# ST_LINK_V3E.net
KiCad netlist of a schematic drawn in Altium Designer
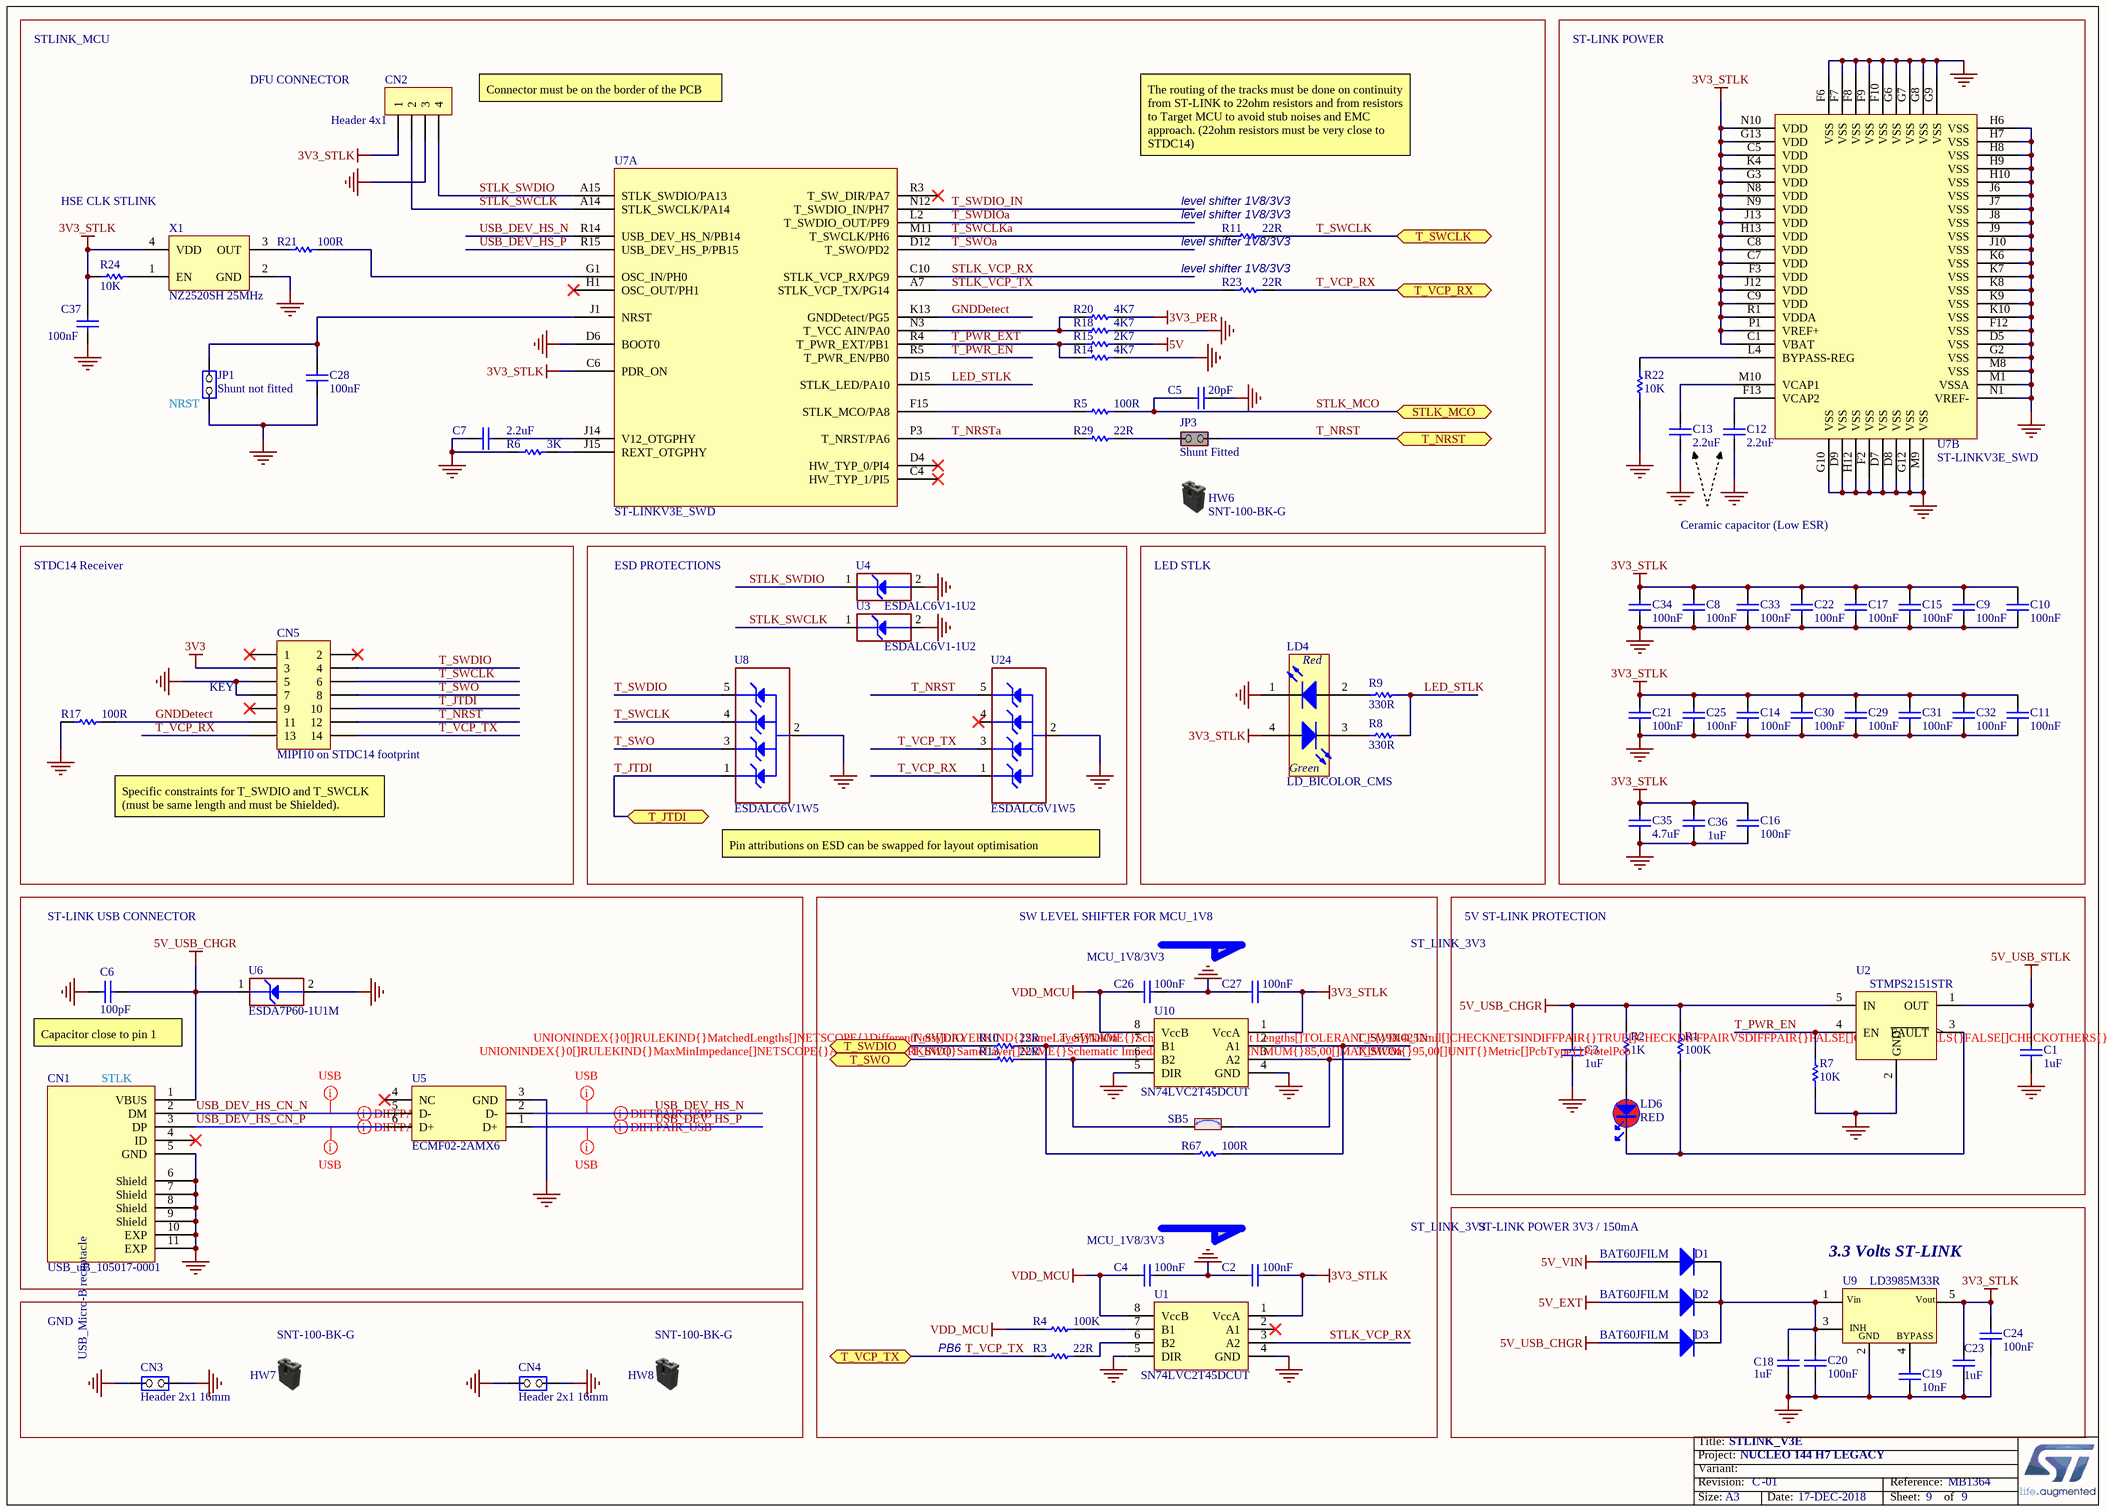
[diagram p0: ST_LINK_V3E.SchDoc]

(export (version "E")
  (design (tool "Eeschema 10.0.6"))
  (components
    (comp (ref "C1")
      (value "1uF")
      (footprint "C0603")
      (description "Capacitor, MLCC, 1uF, 6V3, X5R, 10%, 0603, T=0,8mm")
      (fields
        (field (name "INTERNAL_PART_NUMBER") "MCD-00238")
        (field (name "MANUFACTURER_PART_NUMBER") "CC0603KRX5R5BB105")
        (field (name "PROVIDED_BY") "SUBCO")
      )
      (libsource (lib "MCD_PARTS_database") (part "Capacitor"))
    )
    (comp (ref "C2")
      (value "100nF")
      (footprint "C0603")
      (description "Capacitor, MLCC, 100nF, 6V3, X5R, 10%, 0603, T=0,8mm")
      (fields
        (field (name "INTERNAL_PART_NUMBER") "MCD-00237")
        (field (name "MANUFACTURER_PART_NUMBER") "CC0603KRX5R5BB104")
        (field (name "PROVIDED_BY") "SUBCO")
      )
      (libsource (lib "MCD_PARTS_database") (part "Capacitor"))
    )
    (comp (ref "C3")
      (value "1uF")
      (footprint "C0603")
      (description "Capacitor, MLCC, 1uF, 6V3, X5R, 10%, 0603, T=0,8mm")
      (fields
        (field (name "INTERNAL_PART_NUMBER") "MCD-00238")
        (field (name "MANUFACTURER_PART_NUMBER") "CC0603KRX5R5BB105")
        (field (name "PROVIDED_BY") "SUBCO")
      )
      (libsource (lib "MCD_PARTS_database") (part "Capacitor"))
    )
    (comp (ref "C4")
      (value "100nF")
      (footprint "C0603")
      (description "Capacitor, MLCC, 100nF, 6V3, X5R, 10%, 0603, T=0,8mm")
      (fields
        (field (name "INTERNAL_PART_NUMBER") "MCD-00237")
        (field (name "MANUFACTURER_PART_NUMBER") "CC0603KRX5R5BB104")
        (field (name "PROVIDED_BY") "SUBCO")
      )
      (libsource (lib "MCD_PARTS_database") (part "Capacitor"))
    )
    (comp (ref "C5")
      (value "20pF")
      (footprint "C0402")
      (description "Capacitor, MLCC, 20pF, 50V, NPO, 5%, 0402, T=0,5mm")
      (fields
        (field (name "INTERNAL_PART_NUMBER") "MCD-00016")
        (field (name "MANUFACTURER_PART_NUMBER") "CC0402JRNPO9BN200")
        (field (name "PROVIDED_BY") "SUBCO")
      )
      (libsource (lib "MCD_PARTS_database") (part "Capacitor"))
    )
    (comp (ref "C6")
      (value "100pF")
      (footprint "C0402")
      (description "Capacitor, MLCC, 100pF, 50V, NPO, 5%, 0402, T=0,5mm")
      (fields
        (field (name "INTERNAL_PART_NUMBER") "MCD-00205")
        (field (name "MANUFACTURER_PART_NUMBER") "CC0402JRNPO9BN101")
        (field (name "PROVIDED_BY") "SUBCO")
      )
      (libsource (lib "MCD_PARTS_database") (part "Capacitor"))
    )
    (comp (ref "C7")
      (value "2.2uF")
      (footprint "C0603")
      (description "Capacitor, MLCC, 2.2uF, 10V, X5R, 10%, 0603, T=0,8mm")
      (fields
        (field (name "INTERNAL_PART_NUMBER") "MCD-00012")
        (field (name "MANUFACTURER_PART_NUMBER") "CC0603KRX5R6BB225")
        (field (name "PROVIDED_BY") "SUBCO")
      )
      (libsource (lib "MCD_PARTS_database") (part "Capacitor"))
    )
    (comp (ref "C8")
      (value "100nF")
      (footprint "C0402")
      (description "Capacitor, MLCC, 100nF, 16V, X7R, 10%, 0402, T=0,5mm")
      (fields
        (field (name "INTERNAL_PART_NUMBER") "MCD-00102")
        (field (name "MANUFACTURER_PART_NUMBER") "CC0402KRX7R7BB104")
        (field (name "PROVIDED_BY") "SUBCO")
      )
      (libsource (lib "MCD_PARTS_database") (part "Capacitor"))
    )
    (comp (ref "C9")
      (value "100nF")
      (footprint "C0402")
      (description "Capacitor, MLCC, 100nF, 16V, X7R, 10%, 0402, T=0,5mm")
      (fields
        (field (name "INTERNAL_PART_NUMBER") "MCD-00102")
        (field (name "MANUFACTURER_PART_NUMBER") "CC0402KRX7R7BB104")
        (field (name "PROVIDED_BY") "SUBCO")
      )
      (libsource (lib "MCD_PARTS_database") (part "Capacitor"))
    )
    (comp (ref "C10")
      (value "100nF")
      (footprint "C0402")
      (description "Capacitor, MLCC, 100nF, 16V, X7R, 10%, 0402, T=0,5mm")
      (fields
        (field (name "INTERNAL_PART_NUMBER") "MCD-00102")
        (field (name "MANUFACTURER_PART_NUMBER") "CC0402KRX7R7BB104")
        (field (name "PROVIDED_BY") "SUBCO")
      )
      (libsource (lib "MCD_PARTS_database") (part "Capacitor"))
    )
    (comp (ref "C11")
      (value "100nF")
      (footprint "C0402")
      (description "Capacitor, MLCC, 100nF, 16V, X7R, 10%, 0402, T=0,5mm")
      (fields
        (field (name "INTERNAL_PART_NUMBER") "MCD-00102")
        (field (name "MANUFACTURER_PART_NUMBER") "CC0402KRX7R7BB104")
        (field (name "PROVIDED_BY") "SUBCO")
      )
      (libsource (lib "MCD_PARTS_database") (part "Capacitor"))
    )
    (comp (ref "C12")
      (value "2.2uF")
      (footprint "C0603")
      (description "Capacitor, MLCC, 2.2uF, 10V, X5R, 10%, 0603, T=0,8mm")
      (fields
        (field (name "INTERNAL_PART_NUMBER") "MCD-00012")
        (field (name "MANUFACTURER_PART_NUMBER") "CC0603KRX5R6BB225")
        (field (name "PROVIDED_BY") "SUBCO")
      )
      (libsource (lib "MCD_PARTS_database") (part "Capacitor"))
    )
    (comp (ref "C13")
      (value "2.2uF")
      (footprint "C0603")
      (description "Capacitor, MLCC, 2.2uF, 10V, X5R, 10%, 0603, T=0,8mm")
      (fields
        (field (name "INTERNAL_PART_NUMBER") "MCD-00012")
        (field (name "MANUFACTURER_PART_NUMBER") "CC0603KRX5R6BB225")
        (field (name "PROVIDED_BY") "SUBCO")
      )
      (libsource (lib "MCD_PARTS_database") (part "Capacitor"))
    )
    (comp (ref "C14")
      (value "100nF")
      (footprint "C0402")
      (description "Capacitor, MLCC, 100nF, 16V, X7R, 10%, 0402, T=0,5mm")
      (fields
        (field (name "INTERNAL_PART_NUMBER") "MCD-00102")
        (field (name "MANUFACTURER_PART_NUMBER") "CC0402KRX7R7BB104")
        (field (name "PROVIDED_BY") "SUBCO")
      )
      (libsource (lib "MCD_PARTS_database") (part "Capacitor"))
    )
    (comp (ref "C15")
      (value "100nF")
      (footprint "C0402")
      (description "Capacitor, MLCC, 100nF, 16V, X7R, 10%, 0402, T=0,5mm")
      (fields
        (field (name "INTERNAL_PART_NUMBER") "MCD-00102")
        (field (name "MANUFACTURER_PART_NUMBER") "CC0402KRX7R7BB104")
        (field (name "PROVIDED_BY") "SUBCO")
      )
      (libsource (lib "MCD_PARTS_database") (part "Capacitor"))
    )
    (comp (ref "C16")
      (value "100nF")
      (footprint "C0402")
      (description "Capacitor, MLCC, 100nF, 16V, X7R, 10%, 0402, T=0,5mm")
      (fields
        (field (name "INTERNAL_PART_NUMBER") "MCD-00102")
        (field (name "MANUFACTURER_PART_NUMBER") "CC0402KRX7R7BB104")
        (field (name "PROVIDED_BY") "SUBCO")
      )
      (libsource (lib "MCD_PARTS_database") (part "Capacitor"))
    )
    (comp (ref "C17")
      (value "100nF")
      (footprint "C0402")
      (description "Capacitor, MLCC, 100nF, 16V, X7R, 10%, 0402, T=0,5mm")
      (fields
        (field (name "INTERNAL_PART_NUMBER") "MCD-00102")
        (field (name "MANUFACTURER_PART_NUMBER") "CC0402KRX7R7BB104")
        (field (name "PROVIDED_BY") "SUBCO")
      )
      (libsource (lib "MCD_PARTS_database") (part "Capacitor"))
    )
    (comp (ref "C18")
      (value "1uF")
      (footprint "C0603")
      (description "Capacitor, MLCC, 1uF, 6V3, X5R, 10%, 0603, T=0,8mm")
      (fields
        (field (name "INTERNAL_PART_NUMBER") "MCD-00238")
        (field (name "MANUFACTURER_PART_NUMBER") "CC0603KRX5R5BB105")
        (field (name "PROVIDED_BY") "SUBCO")
      )
      (libsource (lib "MCD_PARTS_database") (part "Capacitor"))
    )
    (comp (ref "C19")
      (value "10nF")
      (footprint "C0402")
      (description "Capacitor, MLCC, 10nF, 16V, X7R, 10%, 0402, T=0.5mm")
      (fields
        (field (name "INTERNAL_PART_NUMBER") "MCD-00011")
        (field (name "MANUFACTURER_PART_NUMBER") "CC0402KRX7R7BB103")
        (field (name "PROVIDED_BY") "SUBCO")
      )
      (libsource (lib "MCD_PARTS_database") (part "Capacitor"))
    )
    (comp (ref "C20")
      (value "100nF")
      (footprint "C0402")
      (description "Capacitor, MLCC, 100nF, 16V, X7R, 10%, 0402, T=0,5mm")
      (fields
        (field (name "INTERNAL_PART_NUMBER") "MCD-00102")
        (field (name "MANUFACTURER_PART_NUMBER") "CC0402KRX7R7BB104")
        (field (name "PROVIDED_BY") "SUBCO")
      )
      (libsource (lib "MCD_PARTS_database") (part "Capacitor"))
    )
    (comp (ref "C21")
      (value "100nF")
      (footprint "C0402")
      (description "Capacitor, MLCC, 100nF, 16V, X7R, 10%, 0402, T=0,5mm")
      (fields
        (field (name "INTERNAL_PART_NUMBER") "MCD-00102")
        (field (name "MANUFACTURER_PART_NUMBER") "CC0402KRX7R7BB104")
        (field (name "PROVIDED_BY") "SUBCO")
      )
      (libsource (lib "MCD_PARTS_database") (part "Capacitor"))
    )
    (comp (ref "C22")
      (value "100nF")
      (footprint "C0402")
      (description "Capacitor, MLCC, 100nF, 16V, X7R, 10%, 0402, T=0,5mm")
      (fields
        (field (name "INTERNAL_PART_NUMBER") "MCD-00102")
        (field (name "MANUFACTURER_PART_NUMBER") "CC0402KRX7R7BB104")
        (field (name "PROVIDED_BY") "SUBCO")
      )
      (libsource (lib "MCD_PARTS_database") (part "Capacitor"))
    )
    (comp (ref "C23")
      (value "1uF")
      (footprint "C0603")
      (description "Capacitor, MLCC, 1uF, 16V, X5R, 10%, 0603, T=0,8mm")
      (fields
        (field (name "INTERNAL_PART_NUMBER") "MCD-00010")
        (field (name "MANUFACTURER_PART_NUMBER") "CC0603KRX5R7BB105")
        (field (name "PROVIDED_BY") "SUBCO")
      )
      (libsource (lib "MCD_PARTS_database") (part "Capacitor"))
    )
    (comp (ref "C24")
      (value "100nF")
      (footprint "C0402")
      (description "Capacitor, MLCC, 100nF, 16V, X7R, 10%, 0402, T=0,5mm")
      (fields
        (field (name "INTERNAL_PART_NUMBER") "MCD-00102")
        (field (name "MANUFACTURER_PART_NUMBER") "CC0402KRX7R7BB104")
        (field (name "PROVIDED_BY") "SUBCO")
      )
      (libsource (lib "MCD_PARTS_database") (part "Capacitor"))
    )
    (comp (ref "C25")
      (value "100nF")
      (footprint "C0402")
      (description "Capacitor, MLCC, 100nF, 16V, X7R, 10%, 0402, T=0,5mm")
      (fields
        (field (name "INTERNAL_PART_NUMBER") "MCD-00102")
        (field (name "MANUFACTURER_PART_NUMBER") "CC0402KRX7R7BB104")
        (field (name "PROVIDED_BY") "SUBCO")
      )
      (libsource (lib "MCD_PARTS_database") (part "Capacitor"))
    )
    (comp (ref "C26")
      (value "100nF")
      (footprint "C0603")
      (description "Capacitor, MLCC, 100nF, 6V3, X5R, 10%, 0603, T=0,8mm")
      (fields
        (field (name "INTERNAL_PART_NUMBER") "MCD-00237")
        (field (name "MANUFACTURER_PART_NUMBER") "CC0603KRX5R5BB104")
        (field (name "PROVIDED_BY") "SUBCO")
      )
      (libsource (lib "MCD_PARTS_database") (part "Capacitor"))
    )
    (comp (ref "C27")
      (value "100nF")
      (footprint "C0603")
      (description "Capacitor, MLCC, 100nF, 6V3, X5R, 10%, 0603, T=0,8mm")
      (fields
        (field (name "INTERNAL_PART_NUMBER") "MCD-00237")
        (field (name "MANUFACTURER_PART_NUMBER") "CC0603KRX5R5BB104")
        (field (name "PROVIDED_BY") "SUBCO")
      )
      (libsource (lib "MCD_PARTS_database") (part "Capacitor"))
    )
    (comp (ref "C28")
      (value "100nF")
      (footprint "C0402")
      (description "Capacitor, MLCC, 100nF, 16V, X7R, 10%, 0402, T=0,5mm")
      (fields
        (field (name "INTERNAL_PART_NUMBER") "MCD-00102")
        (field (name "MANUFACTURER_PART_NUMBER") "CC0402KRX7R7BB104")
        (field (name "PROVIDED_BY") "SUBCO")
      )
      (libsource (lib "MCD_PARTS_database") (part "Capacitor"))
    )
    (comp (ref "C29")
      (value "100nF")
      (footprint "C0402")
      (description "Capacitor, MLCC, 100nF, 16V, X7R, 10%, 0402, T=0,5mm")
      (fields
        (field (name "INTERNAL_PART_NUMBER") "MCD-00102")
        (field (name "MANUFACTURER_PART_NUMBER") "CC0402KRX7R7BB104")
        (field (name "PROVIDED_BY") "SUBCO")
      )
      (libsource (lib "MCD_PARTS_database") (part "Capacitor"))
    )
    (comp (ref "C30")
      (value "100nF")
      (footprint "C0402")
      (description "Capacitor, MLCC, 100nF, 16V, X7R, 10%, 0402, T=0,5mm")
      (fields
        (field (name "INTERNAL_PART_NUMBER") "MCD-00102")
        (field (name "MANUFACTURER_PART_NUMBER") "CC0402KRX7R7BB104")
        (field (name "PROVIDED_BY") "SUBCO")
      )
      (libsource (lib "MCD_PARTS_database") (part "Capacitor"))
    )
    (comp (ref "C31")
      (value "100nF")
      (footprint "C0402")
      (description "Capacitor, MLCC, 100nF, 16V, X7R, 10%, 0402, T=0,5mm")
      (fields
        (field (name "INTERNAL_PART_NUMBER") "MCD-00102")
        (field (name "MANUFACTURER_PART_NUMBER") "CC0402KRX7R7BB104")
        (field (name "PROVIDED_BY") "SUBCO")
      )
      (libsource (lib "MCD_PARTS_database") (part "Capacitor"))
    )
    (comp (ref "C32")
      (value "100nF")
      (footprint "C0402")
      (description "Capacitor, MLCC, 100nF, 16V, X7R, 10%, 0402, T=0,5mm")
      (fields
        (field (name "INTERNAL_PART_NUMBER") "MCD-00102")
        (field (name "MANUFACTURER_PART_NUMBER") "CC0402KRX7R7BB104")
        (field (name "PROVIDED_BY") "SUBCO")
      )
      (libsource (lib "MCD_PARTS_database") (part "Capacitor"))
    )
    (comp (ref "C33")
      (value "100nF")
      (footprint "C0402")
      (description "Capacitor, MLCC, 100nF, 16V, X7R, 10%, 0402, T=0,5mm")
      (fields
        (field (name "INTERNAL_PART_NUMBER") "MCD-00102")
        (field (name "MANUFACTURER_PART_NUMBER") "CC0402KRX7R7BB104")
        (field (name "PROVIDED_BY") "SUBCO")
      )
      (libsource (lib "MCD_PARTS_database") (part "Capacitor"))
    )
    (comp (ref "C34")
      (value "100nF")
      (footprint "C0402")
      (description "Capacitor, MLCC, 100nF, 16V, X7R, 10%, 0402, T=0,5mm")
      (fields
        (field (name "INTERNAL_PART_NUMBER") "MCD-00102")
        (field (name "MANUFACTURER_PART_NUMBER") "CC0402KRX7R7BB104")
        (field (name "PROVIDED_BY") "SUBCO")
      )
      (libsource (lib "MCD_PARTS_database") (part "Capacitor"))
    )
    (comp (ref "C35")
      (value "4.7uF")
      (footprint "C0603")
      (description "Capacitor, MLCC, 4.7uF, 16V, X5R, 10%, 0603, T=0.8mm")
      (fields
        (field (name "INTERNAL_PART_NUMBER") "MCD-00009")
        (field (name "MANUFACTURER_PART_NUMBER") "CC0603KRX5R7BB475")
        (field (name "PROVIDED_BY") "SUBCO")
      )
      (libsource (lib "MCD_PARTS_database") (part "Capacitor"))
    )
    (comp (ref "C36")
      (value "1uF")
      (footprint "C0603")
      (description "Capacitor, MLCC, 1uF, 16V, X5R, 10%, 0603, T=0,8mm")
      (fields
        (field (name "INTERNAL_PART_NUMBER") "MCD-00010")
        (field (name "MANUFACTURER_PART_NUMBER") "CC0603KRX5R7BB105")
        (field (name "PROVIDED_BY") "SUBCO")
      )
      (libsource (lib "MCD_PARTS_database") (part "Capacitor"))
    )
    (comp (ref "C37")
      (value "100nF")
      (footprint "C0402")
      (description "Capacitor, MLCC, 100nF, 16V, X7R, 10%, 0402, T=0,5mm")
      (fields
        (field (name "INTERNAL_PART_NUMBER") "MCD-00102")
        (field (name "MANUFACTURER_PART_NUMBER") "CC0402KRX7R7BB104")
        (field (name "PROVIDED_BY") "SUBCO")
      )
      (libsource (lib "MCD_PARTS_database") (part "Capacitor"))
    )
    (comp (ref "CN1")
      (value "USB_uB_105017-0001")
      (footprint "CON_USBMICROB_MOLEX_105017-0001_H2P90")
      (description "USB-MICRO-B, 0.65mm, RA, SMT, Bottom Mount,")
      (fields
        (field (name "INTERNAL_PART_NUMBER") "MCD-00028")
        (field (name "MANUFACTURER_PART_NUMBER") "1050170001")
        (field (name "PROVIDED_BY") "SUBCO")
      )
      (libsource (lib "MCD_PARTS_database") (part "USB_uB_105017.0001"))
    )
    (comp (ref "CN2")
      (value "Header 4x1")
      (footprint "CON_SAMTEC_TSW-104-07-G-S")
      (description "Header, 4x1, 2,54mm, VR, TH, Height 5.84mm/2.54mm")
      (fields
        (field (name "INTERNAL_PART_NUMBER") "MCD-00029")
        (field (name "MANUFACTURER_PART_NUMBER") "TSW-104-07-x-S")
        (field (name "PROVIDED_BY") "SUBCO")
      )
      (libsource (lib "MCD_PARTS_database") (part "Header 4x1"))
    )
    (comp (ref "CN3")
      (value "Header 2x1 16mm")
      (footprint "CON_SAMTEC_TSW-102-09-X-S")
      (description "Header, 2x1, 2,54mm, VR, TH, Height 5.84mm/10.16mm")
      (fields
        (field (name "INTERNAL_PART_NUMBER") "MCD-00214")
        (field (name "MANUFACTURER_PART_NUMBER") "TSW-102-09-x-S")
        (field (name "PROVIDED_BY") "SUBCO")
      )
      (libsource (lib "MCD_PARTS_database") (part "Jumper_Header 2x1"))
    )
    (comp (ref "CN4")
      (value "Header 2x1 16mm")
      (footprint "CON_SAMTEC_TSW-102-09-X-S")
      (description "Header, 2x1, 2,54mm, VR, TH, Height 5.84mm/10.16mm")
      (fields
        (field (name "INTERNAL_PART_NUMBER") "MCD-00214")
        (field (name "MANUFACTURER_PART_NUMBER") "TSW-102-09-x-S")
        (field (name "PROVIDED_BY") "SUBCO")
      )
      (libsource (lib "MCD_PARTS_database") (part "Jumper_Header 2x1"))
    )
    (comp (ref "CN5")
      (value "MIPI10 on STDC14 footprint")
      (footprint "CON_STDC14_Receiver_MEDIUM_WITH_MIPI10_3D")
      (fields
        (field (name "INTERNAL_PART_NUMBER") "MCD-01226")
        (field (name "MANUFACTURER_PART_NUMBER") "FTSH-105-01-L-DV-K")
        (field (name "MANUFACTURER") "SAMTEC")
        (field (name "PROVIDED_BY") "SUBCO")
      )
      (libsource (lib "MCD_PARTS_database") (part "Header 7x2"))
    )
    (comp (ref "D1")
      (value "BAT60JFILM")
      (footprint "DIO_SOD323")
      (fields
        (field (name "INTERNAL_PART_NUMBER") "MCD-00034")
        (field (name "MANUFACTURER") "STMICROELECTRONICS")
        (field (name "BMS_PART_NUMBER") "9151097")
        (field (name "PROVIDED_BY") "SUBCO with ST control")
      )
      (libsource (lib "MCD_PARTS_database") (part "BAT60JFILM"))
    )
    (comp (ref "D2")
      (value "BAT60JFILM")
      (footprint "DIO_SOD323")
      (fields
        (field (name "INTERNAL_PART_NUMBER") "MCD-00034")
        (field (name "MANUFACTURER") "STMICROELECTRONICS")
        (field (name "BMS_PART_NUMBER") "9151097")
        (field (name "PROVIDED_BY") "SUBCO with ST control")
      )
      (libsource (lib "MCD_PARTS_database") (part "BAT60JFILM"))
    )
    (comp (ref "D3")
      (value "BAT60JFILM")
      (footprint "DIO_SOD323")
      (fields
        (field (name "INTERNAL_PART_NUMBER") "MCD-00034")
        (field (name "MANUFACTURER") "STMICROELECTRONICS")
        (field (name "BMS_PART_NUMBER") "9151097")
        (field (name "PROVIDED_BY") "SUBCO with ST control")
      )
      (libsource (lib "MCD_PARTS_database") (part "BAT60JFILM"))
    )
    (comp (ref "HW6")
      (value "SNT-100-BK-G")
      (description "SHUNT 2.54mm BLACK")
      (fields
        (field (name "INTERNAL_PART_NUMBER") "MCD-00043")
        (field (name "MANUFACTURER") "SAMTEC")
        (field (name "PROVIDED_BY") "SUBCO")
      )
      (libsource (lib "MCD_PARTS_database") (part "Shunt Black 2.54mm"))
    )
    (comp (ref "HW7")
      (value "SNT-100-BK-G")
      (description "SHUNT 2.54mm BLACK")
      (fields
        (field (name "INTERNAL_PART_NUMBER") "MCD-00043")
        (field (name "MANUFACTURER") "SAMTEC")
        (field (name "PROVIDED_BY") "SUBCO")
      )
      (libsource (lib "MCD_PARTS_database") (part "Shunt Black 2.54mm"))
    )
    (comp (ref "HW8")
      (value "SNT-100-BK-G")
      (description "SHUNT 2.54mm BLACK")
      (fields
        (field (name "INTERNAL_PART_NUMBER") "MCD-00043")
        (field (name "MANUFACTURER") "SAMTEC")
        (field (name "PROVIDED_BY") "SUBCO")
      )
      (libsource (lib "MCD_PARTS_database") (part "Shunt Black 2.54mm"))
    )
    (comp (ref "JP1")
      (value "Shunt not fitted")
      (footprint "CON_SAMTEC_TSW-102-07-G-S")
      (description "Header, 2x1, 2,54mm, VR, TH, Height 5.84mm/2.54mm")
      (fields
        (field (name "INTERNAL_PART_NUMBER") "MCD-00045")
        (field (name "MANUFACTURER_PART_NUMBER") "TSW-102-07-x-S")
        (field (name "PROVIDED_BY") "SUBCO")
      )
      (libsource (lib "MCD_PARTS_database") (part "Jumper_Header 2x1"))
    )
    (comp (ref "JP3")
      (value "Shunt Fitted")
      (footprint "CON_SAMTEC_TSW-102-07-G-S")
      (description "Header, 2x1, 2,54mm, VR, TH, Height 5.84mm/2.54mm - Shunt Fitted by default")
      (fields
        (field (name "INTERNAL_PART_NUMBER") "MCD-00683")
        (field (name "MANUFACTURER_PART_NUMBER") "TSW-102-07-x-S")
        (field (name "PROVIDED_BY") "SUBCO")
      )
      (libsource (lib "MCD_PARTS_database") (part "Jumper_Header 2x1 Fitted"))
    )
    (comp (ref "LD4")
      (value "LD_BICOLOR_CMS")
      (footprint "LED_BI-GR_HSMF-A201-A00J1")
      (description "LED Bicolor")
      (fields
        (field (name "INTERNAL_PART_NUMBER") "MCD-00051")
        (field (name "MANUFACTURER_PART_NUMBER") "HSMF-A201-A00J1")
        (field (name "PROVIDED_BY") "SUBCO")
      )
      (libsource (lib "MCD_PARTS_database") (part "LD_BICOLOR_CMS"))
    )
    (comp (ref "LD6")
      (value "RED")
      (footprint "LED_0603_RED")
      (description "LED, Red, 0603")
      (fields
        (field (name "INTERNAL_PART_NUMBER") "MCD-00049")
        (field (name "MANUFACTURER_PART_NUMBER") "19-213-R6C-AP1Q2B/3T")
        (field (name "PROVIDED_BY") "SUBCO")
      )
      (libsource (lib "MCD_PARTS_database") (part "LED_red"))
    )
    (comp (ref "R1")
      (value "100K")
      (footprint "R0603")
      (description "Resistor,100K,0603,1%,1/10W")
      (fields
        (field (name "INTERNAL_PART_NUMBER") "MCD-00223")
        (field (name "MANUFACTURER_PART_NUMBER") "RC0603FR-07100KL")
        (field (name "PROVIDED_BY") "SUBCO")
      )
      (libsource (lib "MCD_PARTS_database") (part "Resistor"))
    )
    (comp (ref "R2")
      (value "1K")
      (footprint "R0603")
      (description "Resistor,1K,0603,1%,1/10W")
      (fields
        (field (name "INTERNAL_PART_NUMBER") "MCD-00070")
        (field (name "MANUFACTURER_PART_NUMBER") "RC0603FR-071KL")
        (field (name "PROVIDED_BY") "SUBCO")
      )
      (libsource (lib "MCD_PARTS_database") (part "Resistor"))
    )
    (comp (ref "R3")
      (value "22R")
      (footprint "R0402")
      (description "Resistor,22R,0402,1%,1/16W")
      (fields
        (field (name "INTERNAL_PART_NUMBER") "MCD-00189")
        (field (name "MANUFACTURER_PART_NUMBER") "RC0402FR-0722RL")
        (field (name "PROVIDED_BY") "SUBCO")
      )
      (libsource (lib "MCD_PARTS_database") (part "Resistor"))
    )
    (comp (ref "R4")
      (value "100K")
      (footprint "R0603")
      (description "Resistor,100K,0603,1%,1/10W")
      (fields
        (field (name "INTERNAL_PART_NUMBER") "MCD-00223")
        (field (name "MANUFACTURER_PART_NUMBER") "RC0603FR-07100KL")
        (field (name "PROVIDED_BY") "SUBCO")
      )
      (libsource (lib "MCD_PARTS_database") (part "Resistor"))
    )
    (comp (ref "R5")
      (value "100R")
      (footprint "R0402")
      (description "Resistor,100R,0402,1%,1/16W")
      (fields
        (field (name "INTERNAL_PART_NUMBER") "MCD-00119")
        (field (name "MANUFACTURER_PART_NUMBER") "RC0402FR-07100RL")
        (field (name "PROVIDED_BY") "SUBCO")
      )
      (libsource (lib "MCD_PARTS_database") (part "Resistor"))
    )
    (comp (ref "R6")
      (value "3K")
      (footprint "R0402")
      (description "Resistor,3K,0402,1%,1/16W")
      (fields
        (field (name "INTERNAL_PART_NUMBER") "MCD-00185")
        (field (name "MANUFACTURER_PART_NUMBER") "RC0402FR-073KL")
        (field (name "PROVIDED_BY") "SUBCO")
      )
      (libsource (lib "MCD_PARTS_database") (part "Resistor"))
    )
    (comp (ref "R7")
      (value "10K")
      (footprint "R0603")
      (description "Resistor,10K,0603,1%,1/10W")
      (fields
        (field (name "INTERNAL_PART_NUMBER") "MCD-00220")
        (field (name "MANUFACTURER_PART_NUMBER") "RC0603FR-0710KL")
        (field (name "PROVIDED_BY") "SUBCO")
      )
      (libsource (lib "MCD_PARTS_database") (part "Resistor"))
    )
    (comp (ref "R8")
      (value "330R")
      (footprint "R0603")
      (description "Resistor,330R,0603,1%,1/10W")
      (fields
        (field (name "INTERNAL_PART_NUMBER") "MCD-00197")
        (field (name "MANUFACTURER_PART_NUMBER") "RC0603FR-07330RL")
        (field (name "PROVIDED_BY") "SUBCO")
      )
      (libsource (lib "MCD_PARTS_database") (part "Resistor"))
    )
    (comp (ref "R9")
      (value "330R")
      (footprint "R0603")
      (description "Resistor,330R,0603,1%,1/10W")
      (fields
        (field (name "INTERNAL_PART_NUMBER") "MCD-00197")
        (field (name "MANUFACTURER_PART_NUMBER") "RC0603FR-07330RL")
        (field (name "PROVIDED_BY") "SUBCO")
      )
      (libsource (lib "MCD_PARTS_database") (part "Resistor"))
    )
    (comp (ref "R10")
      (value "22R")
      (footprint "R0402")
      (description "Resistor,22R,0402,1%,1/16W")
      (fields
        (field (name "INTERNAL_PART_NUMBER") "MCD-00189")
        (field (name "MANUFACTURER_PART_NUMBER") "RC0402FR-0722RL")
        (field (name "PROVIDED_BY") "SUBCO")
      )
      (libsource (lib "MCD_PARTS_database") (part "Resistor"))
    )
    (comp (ref "R11")
      (value "22R")
      (footprint "R0402")
      (description "Resistor,22R,0402,1%,1/16W")
      (fields
        (field (name "INTERNAL_PART_NUMBER") "MCD-00189")
        (field (name "MANUFACTURER_PART_NUMBER") "RC0402FR-0722RL")
        (field (name "PROVIDED_BY") "SUBCO")
      )
      (libsource (lib "MCD_PARTS_database") (part "Resistor"))
    )
    (comp (ref "R13")
      (value "22R")
      (footprint "R0402")
      (description "Resistor,22R,0402,1%,1/16W")
      (fields
        (field (name "INTERNAL_PART_NUMBER") "MCD-00189")
        (field (name "MANUFACTURER_PART_NUMBER") "RC0402FR-0722RL")
        (field (name "PROVIDED_BY") "SUBCO")
      )
      (libsource (lib "MCD_PARTS_database") (part "Resistor"))
    )
    (comp (ref "R14")
      (value "4K7")
      (footprint "R0402")
      (description "Resistor,4K7,0402,1%,1/16W")
      (fields
        (field (name "INTERNAL_PART_NUMBER") "MCD-00065")
        (field (name "MANUFACTURER_PART_NUMBER") "RC0402FR-074K7L")
        (field (name "PROVIDED_BY") "SUBCO")
      )
      (libsource (lib "MCD_PARTS_database") (part "Resistor"))
    )
    (comp (ref "R15")
      (value "2K7")
      (footprint "R0402")
      (description "Resistor,2K7,0402,1%,1/16W")
      (fields
        (field (name "INTERNAL_PART_NUMBER") "MCD-00055")
        (field (name "MANUFACTURER_PART_NUMBER") "RC0402FR-072K7L")
        (field (name "PROVIDED_BY") "SUBCO")
      )
      (libsource (lib "MCD_PARTS_database") (part "Resistor"))
    )
    (comp (ref "R17")
      (value "100R")
      (footprint "R0402")
      (description "Resistor,100R,0402,1%,1/16W")
      (fields
        (field (name "INTERNAL_PART_NUMBER") "MCD-00119")
        (field (name "MANUFACTURER_PART_NUMBER") "RC0402FR-07100RL")
        (field (name "PROVIDED_BY") "SUBCO")
      )
      (libsource (lib "MCD_PARTS_database") (part "Resistor"))
    )
    (comp (ref "R18")
      (value "4K7")
      (footprint "R0402")
      (description "Resistor,4K7,0402,1%,1/16W")
      (fields
        (field (name "INTERNAL_PART_NUMBER") "MCD-00065")
        (field (name "MANUFACTURER_PART_NUMBER") "RC0402FR-074K7L")
        (field (name "PROVIDED_BY") "SUBCO")
      )
      (libsource (lib "MCD_PARTS_database") (part "Resistor"))
    )
    (comp (ref "R20")
      (value "4K7")
      (footprint "R0402")
      (description "Resistor,4K7,0402,1%,1/16W")
      (fields
        (field (name "INTERNAL_PART_NUMBER") "MCD-00065")
        (field (name "MANUFACTURER_PART_NUMBER") "RC0402FR-074K7L")
        (field (name "PROVIDED_BY") "SUBCO")
      )
      (libsource (lib "MCD_PARTS_database") (part "Resistor"))
    )
    (comp (ref "R21")
      (value "100R")
      (footprint "R0402")
      (description "Resistor,100R,0402,1%,1/16W")
      (fields
        (field (name "INTERNAL_PART_NUMBER") "MCD-00119")
        (field (name "MANUFACTURER_PART_NUMBER") "RC0402FR-07100RL")
        (field (name "PROVIDED_BY") "SUBCO")
      )
      (libsource (lib "MCD_PARTS_database") (part "Resistor"))
    )
    (comp (ref "R22")
      (value "10K")
      (footprint "R0402")
      (description "Resistor,10K,0402,1%,1/16W")
      (fields
        (field (name "INTERNAL_PART_NUMBER") "MCD-00053")
        (field (name "MANUFACTURER_PART_NUMBER") "RC0402FR-0710KL")
        (field (name "PROVIDED_BY") "SUBCO")
      )
      (libsource (lib "MCD_PARTS_database") (part "Resistor"))
    )
    (comp (ref "R23")
      (value "22R")
      (footprint "R0402")
      (description "Resistor,22R,0402,1%,1/16W")
      (fields
        (field (name "INTERNAL_PART_NUMBER") "MCD-00189")
        (field (name "MANUFACTURER_PART_NUMBER") "RC0402FR-0722RL")
        (field (name "PROVIDED_BY") "SUBCO")
      )
      (libsource (lib "MCD_PARTS_database") (part "Resistor"))
    )
    (comp (ref "R24")
      (value "10K")
      (footprint "R0402")
      (description "Resistor,10K,0402,1%,1/16W")
      (fields
        (field (name "INTERNAL_PART_NUMBER") "MCD-00053")
        (field (name "MANUFACTURER_PART_NUMBER") "RC0402FR-0710KL")
        (field (name "PROVIDED_BY") "SUBCO")
      )
      (libsource (lib "MCD_PARTS_database") (part "Resistor"))
    )
    (comp (ref "R29")
      (value "22R")
      (footprint "R0402")
      (description "Resistor,22R,0402,1%,1/16W")
      (fields
        (field (name "INTERNAL_PART_NUMBER") "MCD-00189")
        (field (name "MANUFACTURER_PART_NUMBER") "RC0402FR-0722RL")
        (field (name "PROVIDED_BY") "SUBCO")
      )
      (libsource (lib "MCD_PARTS_database") (part "Resistor"))
    )
    (comp (ref "R67")
      (value "100R")
      (footprint "R0402")
      (description "Resistor,100R,0402,1%,1/16W")
      (fields
        (field (name "INTERNAL_PART_NUMBER") "MCD-00119")
        (field (name "MANUFACTURER_PART_NUMBER") "RC0402FR-07100RL")
        (field (name "PROVIDED_BY") "SUBCO")
      )
      (libsource (lib "MCD_PARTS_database") (part "Resistor"))
    )
    (comp (ref "SB5")
      (value "SB_ON")
      (footprint "SOLDER-BRIDGE_R0603-0R")
      (description "Solder Bridge ON")
      (fields
        (field (name "INTERNAL_PART_NUMBER") "MCD-00071")
        (field (name "MANUFACTURER_PART_NUMBER") "RC0603JR-070RL")
        (field (name "PROVIDED_BY") "SUBCO")
      )
      (libsource (lib "MCD_PARTS_database") (part "SB_ON"))
    )
    (comp (ref "U1")
      (value "SN74LVC2T45DCUT")
      (footprint "ICC_VSSOP8_DCU_R-PDSO-G8_2X2P30_P050")
      (description "Dual bit dual supply bus transceiver")
      (fields
        (field (name "INTERNAL_PART_NUMBER") "MCD-00264")
        (field (name "MANUFACTURER") "TEXAS INSTRUMENTS")
        (field (name "PROVIDED_BY") "SUBCO")
      )
      (libsource (lib "MCD_PARTS_database") (part "SN74LVC2T45DCUT"))
    )
    (comp (ref "U2")
      (value "STMPS2151STR")
      (footprint "MOS_SOT23-5L")
      (description "500mA, Enhanced single channel power switches with active high enable pin")
      (fields
        (field (name "INTERNAL_PART_NUMBER") "MCD-00159")
        (field (name "MANUFACTURER") "STMICROELECTRONICS")
        (field (name "PROVIDED_BY") "SUBCO with ST control")
      )
      (libsource (lib "MCD_PARTS_database") (part "STMPS2151STR"))
    )
    (comp (ref "U3")
      (value "ESDALC6V1-1U2")
      (footprint "ESD_ST0201")
      (description "ESD protection 6V1")
      (fields
        (field (name "INTERNAL_PART_NUMBER") "MCD-00170")
        (field (name "MANUFACTURER") "STMICROELECTRONICS")
        (field (name "PROVIDED_BY") "SUBCO with ST control")
      )
      (libsource (lib "MCD_PARTS_database") (part "ESD-TRANSIL"))
    )
    (comp (ref "U4")
      (value "ESDALC6V1-1U2")
      (footprint "ESD_ST0201")
      (description "ESD protection 6V1")
      (fields
        (field (name "INTERNAL_PART_NUMBER") "MCD-00170")
        (field (name "MANUFACTURER") "STMICROELECTRONICS")
        (field (name "PROVIDED_BY") "SUBCO with ST control")
      )
      (libsource (lib "MCD_PARTS_database") (part "ESD-TRANSIL"))
    )
    (comp (ref "U5")
      (value "ECMF02-2AMX6")
      (footprint "ESD_QFN-6L_1P7X1P5_P050")
      (description "Common mode filter with ESD protection for USB 2.0 interface")
      (fields
        (field (name "INTERNAL_PART_NUMBER") "MCD-00649")
        (field (name "MANUFACTURER") "STMICROELECTRONICS")
        (field (name "PROVIDED_BY") "SUBCO with ST control")
      )
      (libsource (lib "MCD_PARTS_database") (part "ECMF02-2AMX6"))
    )
    (comp (ref "U6")
      (value "ESDA7P60-1U1M")
      (footprint "ESD_QFN2_1P6X1_P125")
      (description "High power transient voltage suppressor, 7V breakdown")
      (fields
        (field (name "INTERNAL_PART_NUMBER") "MCD-00251")
        (field (name "MANUFACTURER") "STMICROELECTRONICS")
        (field (name "PROVIDED_BY") "SUBCO with ST control")
      )
      (libsource (lib "MCD_PARTS_database") (part "ESD-TRANSIL"))
    )
    (comp (ref "U7")
      (value "ST-LINKV3E_SWD")
      (footprint "ICC_UFBGA201_176+25_10X10_P065")
      (description "STM32F723IEK  (STM32F7) BGA176")
      (fields
        (field (name "INTERNAL_PART_NUMBER") "MCD-00596")
        (field (name "MANUFACTURER_PART_NUMBER") "STM32F723IEK6")
        (field (name "PROVIDED_BY") "SUBCO with ST control")
      )
      (libsource (lib "MCD_PARTS_database") (part "ST-LINKV3E_SWD"))
    )
    (comp (ref "U8")
      (value "ESDALC6V1W5")
      (footprint "ESD_SOT323-5L")
      (description "Dual Transil array for ESD protection")
      (fields
        (field (name "INTERNAL_PART_NUMBER") "MCD-00136")
        (field (name "MANUFACTURER") "STMICROELECTRONICS")
        (field (name "PROVIDED_BY") "SUBCO with ST control")
      )
      (libsource (lib "MCD_PARTS_database") (part "ESDALC6V1W5"))
    )
    (comp (ref "U9")
      (value "LD3985M33R")
      (footprint "REG_SOT23-5L")
      (description "Ultra low drop-low noise BiCMOS voltage, regulators low ESR capacitors compatible")
      (fields
        (field (name "INTERNAL_PART_NUMBER") "MCD-00086")
        (field (name "MANUFACTURER") "STMICROELECTRONICS")
        (field (name "PROVIDED_BY") "SUBCO with ST control")
      )
      (libsource (lib "MCD_PARTS_database") (part "LD3985M33R"))
    )
    (comp (ref "U10")
      (value "SN74LVC2T45DCUT")
      (footprint "ICC_VSSOP8_DCU_R-PDSO-G8_2X2P30_P050")
      (description "Dual bit dual supply bus transceiver")
      (fields
        (field (name "INTERNAL_PART_NUMBER") "MCD-00264")
        (field (name "MANUFACTURER") "TEXAS INSTRUMENTS")
        (field (name "PROVIDED_BY") "SUBCO")
      )
      (libsource (lib "MCD_PARTS_database") (part "SN74LVC2T45DCUT"))
    )
    (comp (ref "U24")
      (value "ESDALC6V1W5")
      (footprint "ESD_SOT323-5L")
      (description "Dual Transil array for ESD protection")
      (fields
        (field (name "INTERNAL_PART_NUMBER") "MCD-00136")
        (field (name "MANUFACTURER") "STMICROELECTRONICS")
        (field (name "PROVIDED_BY") "SUBCO with ST control")
      )
      (libsource (lib "MCD_PARTS_database") (part "ESDALC6V1W5"))
    )
    (comp (ref "X1")
      (value "NZ2520SH 25MHz")
      (footprint "OSC_NDK_NZ2520SB_4P")
      (description "Oscillator 25Mhz, +-50ppm, Vcc:3.3V typ, square wave: [0.1Vcc;0.9Vcc], Enable pin, SMD")
      (fields
        (field (name "INTERNAL_PART_NUMBER") "MCD-00597")
        (field (name "MANUFACTURER_PART_NUMBER") "NZ2520SH 25MHz END4869C")
        (field (name "PROVIDED_BY") "SUBCO")
      )
      (libsource (lib "MCD_PARTS_database") (part "OSCILLATOR_4_PINS"))
    )
  )
  (nets
    (net (code "2") (name "/GNDDetect") (class "Default")
      (node (ref "CN5") (pin "11") (pinfunction "11_11") (pintype "passive"))
      (node (ref "R17") (pin "2") (pinfunction "2_2") (pintype "passive"))
      (node (ref "U7") (pin "K13") (pinfunction "GNDDetect/PG5_K13") (pintype "passive"))
    )
    (net (code "3") (name "/LED_STLK") (class "Default")
      (node (ref "R8") (pin "2") (pinfunction "2_2") (pintype "passive"))
      (node (ref "R9") (pin "2") (pinfunction "2_2") (pintype "passive"))
      (node (ref "U7") (pin "D15") (pinfunction "STLK_LED/PA10_D15") (pintype "passive"))
    )
    (net (code "4") (name "/STLK_MCO") (class "Default")
      (node (ref "C5") (pin "2") (pinfunction "2_2") (pintype "passive"))
      (node (ref "R5") (pin "2") (pinfunction "2_2") (pintype "passive"))
    )
    (net (code "5") (name "/STLK_SWCLK") (class "Default")
      (node (ref "CN2") (pin "2") (pinfunction "2_2") (pintype "passive"))
      (node (ref "U3") (pin "1") (pinfunction "IO1_1") (pintype "passive"))
      (node (ref "U7") (pin "A14") (pinfunction "STLK_SWCLK/PA14_A14") (pintype "passive"))
    )
    (net (code "6") (name "/STLK_SWDIO") (class "Default")
      (node (ref "CN2") (pin "4") (pinfunction "4_4") (pintype "passive"))
      (node (ref "U4") (pin "1") (pinfunction "IO1_1") (pintype "passive"))
      (node (ref "U7") (pin "A15") (pinfunction "STLK_SWDIO/PA13_A15") (pintype "passive"))
    )
    (net (code "7") (name "/STLK_VCP_RX") (class "Default")
      (node (ref "U1") (pin "3") (pinfunction "A2_3") (pintype "passive"))
      (node (ref "U7") (pin "C10") (pinfunction "STLK_VCP_RX/PG9_C10") (pintype "passive"))
    )
    (net (code "8") (name "/STLK_VCP_TX") (class "Default")
      (node (ref "R23") (pin "1") (pinfunction "1_1") (pintype "passive"))
      (node (ref "U7") (pin "A7") (pinfunction "STLK_VCP_TX/PG14_A7") (pintype "passive"))
    )
    (net (code "9") (name "/T_JTDI") (class "Default")
      (node (ref "CN5") (pin "10") (pinfunction "10_10") (pintype "passive"))
      (node (ref "U8") (pin "1") (pinfunction "IO1_1") (pintype "passive"))
    )
    (net (code "10") (name "/T_NRST") (class "Default")
      (node (ref "CN5") (pin "12") (pinfunction "12_12") (pintype "passive"))
      (node (ref "JP3") (pin "2") (pinfunction "NO_2") (pintype "passive"))
      (node (ref "U24") (pin "5") (pinfunction "IO4_5") (pintype "passive"))
    )
    (net (code "11") (name "/T_NRSTa") (class "Default")
      (node (ref "R29") (pin "1") (pinfunction "1_1") (pintype "passive"))
      (node (ref "U7") (pin "P3") (pinfunction "T_NRST/PA6_P3") (pintype "passive"))
    )
    (net (code "12") (name "/T_PWR_EN") (class "Default")
      (node (ref "R7") (pin "1") (pinfunction "1_1") (pintype "passive"))
      (node (ref "U2") (pin "4") (pinfunction "EN_4") (pintype "passive"))
      (node (ref "U7") (pin "R5") (pinfunction "T_PWR_EN/PB0_R5") (pintype "passive"))
    )
    (net (code "13") (name "/T_PWR_EXT") (class "Default")
      (node (ref "R14") (pin "2") (pinfunction "2_2") (pintype "passive"))
      (node (ref "R15") (pin "2") (pinfunction "2_2") (pintype "passive"))
      (node (ref "U7") (pin "R4") (pinfunction "T_PWR_EXT/PB1_R4") (pintype "passive"))
    )
    (net (code "14") (name "/T_SWCLK") (class "Default")
      (node (ref "CN5") (pin "6") (pinfunction "6_6") (pintype "passive"))
      (node (ref "R11") (pin "2") (pinfunction "2_2") (pintype "passive"))
      (node (ref "U8") (pin "4") (pinfunction "IO3_4") (pintype "passive"))
    )
    (net (code "15") (name "/T_SWCLKa") (class "Default")
      (node (ref "R11") (pin "1") (pinfunction "1_1") (pintype "passive"))
      (node (ref "U7") (pin "M11") (pinfunction "T_SWCLK/PH6_M11") (pintype "passive"))
    )
    (net (code "16") (name "/T_SWDIO") (class "Default")
      (node (ref "CN5") (pin "4") (pinfunction "4_4") (pintype "passive"))
      (node (ref "R10") (pin "1") (pinfunction "1_1") (pintype "passive"))
      (node (ref "U8") (pin "5") (pinfunction "IO4_5") (pintype "passive"))
    )
    (net (code "17") (name "/T_SWDIO_IN") (class "Default")
      (node (ref "R67") (pin "2") (pinfunction "2_2") (pintype "passive"))
      (node (ref "U10") (pin "2") (pinfunction "A1_2") (pintype "passive"))
      (node (ref "U7") (pin "N12") (pinfunction "T_SWDIO_IN/PH7_N12") (pintype "passive"))
    )
    (net (code "18") (name "/T_SWDIOa") (class "Default")
      (node (ref "R10") (pin "2") (pinfunction "2_2") (pintype "passive"))
      (node (ref "R67") (pin "1") (pinfunction "1_1") (pintype "passive"))
      (node (ref "U10") (pin "7") (pinfunction "B1_7") (pintype "passive"))
      (node (ref "U7") (pin "L2") (pinfunction "T_SWDIO_OUT/PF9_L2") (pintype "passive"))
    )
    (net (code "19") (name "/T_SWO") (class "Default")
      (node (ref "CN5") (pin "8") (pinfunction "8_8") (pintype "passive"))
      (node (ref "R13") (pin "1") (pinfunction "1_1") (pintype "passive"))
      (node (ref "U8") (pin "3") (pinfunction "IO2_3") (pintype "passive"))
    )
    (net (code "20") (name "/T_SWOa") (class "Default")
      (node (ref "SB5") (pin "1") (pinfunction "1_1") (pintype "passive"))
      (node (ref "U10") (pin "3") (pinfunction "A2_3") (pintype "passive"))
      (node (ref "U7") (pin "D12") (pinfunction "T_SWO/PD2_D12") (pintype "passive"))
    )
    (net (code "21") (name "/T_VCP_RX") (class "Default")
      (node (ref "CN5") (pin "13") (pinfunction "13_13") (pintype "passive"))
      (node (ref "R23") (pin "2") (pinfunction "2_2") (pintype "passive"))
      (node (ref "U24") (pin "1") (pinfunction "IO1_1") (pintype "passive"))
    )
    (net (code "22") (name "/T_VCP_TX") (class "Default")
      (node (ref "CN5") (pin "14") (pinfunction "14_14") (pintype "passive"))
      (node (ref "R3") (pin "1") (pinfunction "1_1") (pintype "passive"))
      (node (ref "U24") (pin "3") (pinfunction "IO2_3") (pintype "passive"))
    )
    (net (code "23") (name "/USB_DEV_HS_CN_N") (class "Default")
      (node (ref "CN1") (pin "2") (pinfunction "DM_2") (pintype "passive"))
      (node (ref "U5") (pin "5") (pinfunction "D-_5") (pintype "passive"))
    )
    (net (code "24") (name "/USB_DEV_HS_CN_P") (class "Default")
      (node (ref "CN1") (pin "3") (pinfunction "DP_3") (pintype "passive"))
      (node (ref "U5") (pin "6") (pinfunction "D+_6") (pintype "passive"))
    )
    (net (code "25") (name "/USB_DEV_HS_N") (class "Default")
      (node (ref "U5") (pin "2") (pinfunction "D-_2") (pintype "passive"))
      (node (ref "U7") (pin "R14") (pinfunction "USB_DEV_HS_N/PB14_R14") (pintype "passive"))
    )
    (net (code "26") (name "/USB_DEV_HS_P") (class "Default")
      (node (ref "U5") (pin "1") (pinfunction "D+_1") (pintype "passive"))
      (node (ref "U7") (pin "R15") (pinfunction "USB_DEV_HS_P/PB15_R15") (pintype "passive"))
    )
    (net (code "27") (name "3V3") (class "Default")
      (node (ref "CN5") (pin "3") (pinfunction "3_3") (pintype "passive"))
    )
    (net (code "28") (name "3V3_PER") (class "Default")
      (node (ref "R20") (pin "2") (pinfunction "2_2") (pintype "passive"))
    )
    (net (code "29") (name "3V3_STLK") (class "Default")
      (node (ref "C10") (pin "2") (pinfunction "2_2") (pintype "passive"))
      (node (ref "C11") (pin "2") (pinfunction "2_2") (pintype "passive"))
      (node (ref "C14") (pin "2") (pinfunction "2_2") (pintype "passive"))
      (node (ref "C15") (pin "2") (pinfunction "2_2") (pintype "passive"))
      (node (ref "C16") (pin "2") (pinfunction "2_2") (pintype "passive"))
      (node (ref "C17") (pin "2") (pinfunction "2_2") (pintype "passive"))
      (node (ref "C2") (pin "2") (pinfunction "2_2") (pintype "passive"))
      (node (ref "C21") (pin "2") (pinfunction "2_2") (pintype "passive"))
      (node (ref "C22") (pin "2") (pinfunction "2_2") (pintype "passive"))
      (node (ref "C23") (pin "2") (pinfunction "2_2") (pintype "passive"))
      (node (ref "C24") (pin "2") (pinfunction "2_2") (pintype "passive"))
      (node (ref "C25") (pin "2") (pinfunction "2_2") (pintype "passive"))
      (node (ref "C27") (pin "2") (pinfunction "2_2") (pintype "passive"))
      (node (ref "C29") (pin "2") (pinfunction "2_2") (pintype "passive"))
      (node (ref "C30") (pin "2") (pinfunction "2_2") (pintype "passive"))
      (node (ref "C31") (pin "2") (pinfunction "2_2") (pintype "passive"))
      (node (ref "C32") (pin "2") (pinfunction "2_2") (pintype "passive"))
      (node (ref "C33") (pin "2") (pinfunction "2_2") (pintype "passive"))
      (node (ref "C34") (pin "2") (pinfunction "2_2") (pintype "passive"))
      (node (ref "C35") (pin "2") (pinfunction "2_2") (pintype "passive"))
      (node (ref "C36") (pin "2") (pinfunction "2_2") (pintype "passive"))
      (node (ref "C37") (pin "2") (pinfunction "2_2") (pintype "passive"))
      (node (ref "C8") (pin "2") (pinfunction "2_2") (pintype "passive"))
      (node (ref "C9") (pin "2") (pinfunction "2_2") (pintype "passive"))
      (node (ref "CN2") (pin "1") (pinfunction "1_1") (pintype "passive"))
      (node (ref "LD4") (pin "4") (pinfunction "YellowGreen_anode_4") (pintype "passive"))
      (node (ref "R24") (pin "1") (pinfunction "1_1") (pintype "passive"))
      (node (ref "U1") (pin "1") (pinfunction "VccA_1") (pintype "power_in"))
      (node (ref "U10") (pin "1") (pinfunction "VccA_1") (pintype "power_in"))
      (node (ref "U7") (pin "C1") (pinfunction "VBAT_C1") (pintype "passive"))
      (node (ref "U7") (pin "C5") (pinfunction "VDD_C5") (pintype "passive"))
      (node (ref "U7") (pin "C6") (pinfunction "PDR_ON_C6") (pintype "passive"))
      (node (ref "U7") (pin "C7") (pinfunction "VDD_C7") (pintype "passive"))
      (node (ref "U7") (pin "C8") (pinfunction "VDD_C8") (pintype "passive"))
      (node (ref "U7") (pin "C9") (pinfunction "VDD_C9") (pintype "passive"))
      (node (ref "U7") (pin "F3") (pinfunction "VDD_F3") (pintype "passive"))
      (node (ref "U7") (pin "G13") (pinfunction "VDD_G13") (pintype "passive"))
      (node (ref "U7") (pin "G3") (pinfunction "VDD_G3") (pintype "passive"))
      (node (ref "U7") (pin "H13") (pinfunction "VDD_H13") (pintype "passive"))
      (node (ref "U7") (pin "J12") (pinfunction "VDD_J12") (pintype "passive"))
      (node (ref "U7") (pin "J13") (pinfunction "VDD_J13") (pintype "passive"))
      (node (ref "U7") (pin "K4") (pinfunction "VDD_K4") (pintype "passive"))
      (node (ref "U7") (pin "N10") (pinfunction "VDD_N10") (pintype "passive"))
      (node (ref "U7") (pin "N8") (pinfunction "VDD_N8") (pintype "passive"))
      (node (ref "U7") (pin "N9") (pinfunction "VDD_N9") (pintype "passive"))
      (node (ref "U7") (pin "P1") (pinfunction "VREF+_P1") (pintype "passive"))
      (node (ref "U7") (pin "R1") (pinfunction "VDDA_R1") (pintype "passive"))
      (node (ref "U9") (pin "5") (pinfunction "Vout_5") (pintype "passive"))
      (node (ref "X1") (pin "4") (pinfunction "VDD_4") (pintype "passive"))
    )
    (net (code "30") (name "5V") (class "Default")
      (node (ref "R15") (pin "1") (pinfunction "1_1") (pintype "passive"))
    )
    (net (code "31") (name "5V_EXT") (class "Default")
      (node (ref "D2") (pin "1") (pinfunction "A_1") (pintype "passive"))
    )
    (net (code "32") (name "5V_USB_CHGR") (class "Default")
      (node (ref "C3") (pin "2") (pinfunction "2_2") (pintype "passive"))
      (node (ref "C6") (pin "2") (pinfunction "2_2") (pintype "passive"))
      (node (ref "CN1") (pin "1") (pinfunction "VBUS_1") (pintype "passive"))
      (node (ref "D3") (pin "1") (pinfunction "A_1") (pintype "passive"))
      (node (ref "R1") (pin "2") (pinfunction "2_2") (pintype "passive"))
      (node (ref "R2") (pin "2") (pinfunction "2_2") (pintype "passive"))
      (node (ref "U2") (pin "5") (pinfunction "IN_5") (pintype "passive"))
      (node (ref "U6") (pin "1") (pinfunction "IO1_1") (pintype "passive"))
    )
    (net (code "33") (name "5V_USB_STLK") (class "Default")
      (node (ref "C1") (pin "2") (pinfunction "2_2") (pintype "passive"))
      (node (ref "U2") (pin "1") (pinfunction "OUT_1") (pintype "passive"))
    )
    (net (code "34") (name "5V_VIN") (class "Default")
      (node (ref "D1") (pin "1") (pinfunction "A_1") (pintype "passive"))
    )
    (net (code "35") (name "GND") (class "Default")
      (node (ref "C1") (pin "1") (pinfunction "1_1") (pintype "passive"))
      (node (ref "C10") (pin "1") (pinfunction "1_1") (pintype "passive"))
      (node (ref "C11") (pin "1") (pinfunction "1_1") (pintype "passive"))
      (node (ref "C12") (pin "1") (pinfunction "1_1") (pintype "passive"))
      (node (ref "C13") (pin "1") (pinfunction "1_1") (pintype "passive"))
      (node (ref "C14") (pin "1") (pinfunction "1_1") (pintype "passive"))
      (node (ref "C15") (pin "1") (pinfunction "1_1") (pintype "passive"))
      (node (ref "C16") (pin "1") (pinfunction "1_1") (pintype "passive"))
      (node (ref "C17") (pin "1") (pinfunction "1_1") (pintype "passive"))
      (node (ref "C18") (pin "2") (pinfunction "2_2") (pintype "passive"))
      (node (ref "C19") (pin "1") (pinfunction "1_1") (pintype "passive"))
      (node (ref "C2") (pin "1") (pinfunction "1_1") (pintype "passive"))
      (node (ref "C20") (pin "1") (pinfunction "1_1") (pintype "passive"))
      (node (ref "C21") (pin "1") (pinfunction "1_1") (pintype "passive"))
      (node (ref "C22") (pin "1") (pinfunction "1_1") (pintype "passive"))
      (node (ref "C23") (pin "1") (pinfunction "1_1") (pintype "passive"))
      (node (ref "C24") (pin "1") (pinfunction "1_1") (pintype "passive"))
      (node (ref "C25") (pin "1") (pinfunction "1_1") (pintype "passive"))
      (node (ref "C26") (pin "2") (pinfunction "2_2") (pintype "passive"))
      (node (ref "C27") (pin "1") (pinfunction "1_1") (pintype "passive"))
      (node (ref "C28") (pin "1") (pinfunction "1_1") (pintype "passive"))
      (node (ref "C29") (pin "1") (pinfunction "1_1") (pintype "passive"))
      (node (ref "C3") (pin "1") (pinfunction "1_1") (pintype "passive"))
      (node (ref "C30") (pin "1") (pinfunction "1_1") (pintype "passive"))
      (node (ref "C31") (pin "1") (pinfunction "1_1") (pintype "passive"))
      (node (ref "C32") (pin "1") (pinfunction "1_1") (pintype "passive"))
      (node (ref "C33") (pin "1") (pinfunction "1_1") (pintype "passive"))
      (node (ref "C34") (pin "1") (pinfunction "1_1") (pintype "passive"))
      (node (ref "C35") (pin "1") (pinfunction "1_1") (pintype "passive"))
      (node (ref "C36") (pin "1") (pinfunction "1_1") (pintype "passive"))
      (node (ref "C37") (pin "1") (pinfunction "1_1") (pintype "passive"))
      (node (ref "C4") (pin "2") (pinfunction "2_2") (pintype "passive"))
      (node (ref "C5") (pin "1") (pinfunction "1_1") (pintype "passive"))
      (node (ref "C6") (pin "1") (pinfunction "1_1") (pintype "passive"))
      (node (ref "C7") (pin "1") (pinfunction "1_1") (pintype "passive"))
      (node (ref "C8") (pin "1") (pinfunction "1_1") (pintype "passive"))
      (node (ref "C9") (pin "1") (pinfunction "1_1") (pintype "passive"))
      (node (ref "CN1") (pin "10") (pinfunction "EXP_10") (pintype "passive"))
      (node (ref "CN1") (pin "11") (pinfunction "EXP_11") (pintype "passive"))
      (node (ref "CN1") (pin "5") (pinfunction "GND_5") (pintype "passive"))
      (node (ref "CN1") (pin "6") (pinfunction "Shield_6") (pintype "passive"))
      (node (ref "CN1") (pin "7") (pinfunction "Shield_7") (pintype "passive"))
      (node (ref "CN1") (pin "8") (pinfunction "Shield_8") (pintype "passive"))
      (node (ref "CN1") (pin "9") (pinfunction "Shield_9") (pintype "passive"))
      (node (ref "CN2") (pin "3") (pinfunction "3_3") (pintype "passive"))
      (node (ref "CN3") (pin "1") (pinfunction "COMMON_1") (pintype "passive"))
      (node (ref "CN3") (pin "2") (pinfunction "NO_2") (pintype "passive"))
      (node (ref "CN4") (pin "1") (pinfunction "COMMON_1") (pintype "passive"))
      (node (ref "CN4") (pin "2") (pinfunction "NO_2") (pintype "passive"))
      (node (ref "CN5") (pin "5") (pinfunction "5_5") (pintype "passive"))
      (node (ref "CN5") (pin "7") (pinfunction "7_7") (pintype "passive"))
      (node (ref "JP1") (pin "1") (pinfunction "COMMON_1") (pintype "passive"))
      (node (ref "LD4") (pin "1") (pinfunction "RED_cathode_1") (pintype "passive"))
      (node (ref "R14") (pin "1") (pinfunction "1_1") (pintype "passive"))
      (node (ref "R17") (pin "1") (pinfunction "1_1") (pintype "passive"))
      (node (ref "R18") (pin "2") (pinfunction "2_2") (pintype "passive"))
      (node (ref "R22") (pin "1") (pinfunction "1_1") (pintype "passive"))
      (node (ref "R6") (pin "1") (pinfunction "1_1") (pintype "passive"))
      (node (ref "R7") (pin "2") (pinfunction "2_2") (pintype "passive"))
      (node (ref "U1") (pin "4") (pinfunction "GND_4") (pintype "power_in"))
      (node (ref "U1") (pin "5") (pinfunction "DIR_5") (pintype "passive"))
      (node (ref "U10") (pin "4") (pinfunction "GND_4") (pintype "power_in"))
      (node (ref "U10") (pin "5") (pinfunction "DIR_5") (pintype "passive"))
      (node (ref "U2") (pin "2") (pinfunction "GND_2") (pintype "passive"))
      (node (ref "U24") (pin "2") (pinfunction "GND_2") (pintype "passive"))
      (node (ref "U3") (pin "2") (pinfunction "GND_2") (pintype "passive"))
      (node (ref "U4") (pin "2") (pinfunction "GND_2") (pintype "passive"))
      (node (ref "U5") (pin "3") (pinfunction "GND_3") (pintype "passive"))
      (node (ref "U6") (pin "2") (pinfunction "GND_2") (pintype "passive"))
      (node (ref "U7") (pin "D5") (pinfunction "VSS_D5") (pintype "passive"))
      (node (ref "U7") (pin "D6") (pinfunction "BOOT0_D6") (pintype "passive"))
      (node (ref "U7") (pin "D7") (pinfunction "VSS_D7") (pintype "passive"))
      (node (ref "U7") (pin "D8") (pinfunction "VSS_D8") (pintype "passive"))
      (node (ref "U7") (pin "D9") (pinfunction "VSS_D9") (pintype "passive"))
      (node (ref "U7") (pin "F10") (pinfunction "VSS_F10") (pintype "passive"))
      (node (ref "U7") (pin "F12") (pinfunction "VSS_F12") (pintype "passive"))
      (node (ref "U7") (pin "F2") (pinfunction "VSS_F2") (pintype "passive"))
      (node (ref "U7") (pin "F6") (pinfunction "VSS_F6") (pintype "passive"))
      (node (ref "U7") (pin "F7") (pinfunction "VSS_F7") (pintype "passive"))
      (node (ref "U7") (pin "F8") (pinfunction "VSS_F8") (pintype "passive"))
      (node (ref "U7") (pin "F9") (pinfunction "VSS_F9") (pintype "passive"))
      (node (ref "U7") (pin "G10") (pinfunction "VSS_G10") (pintype "passive"))
      (node (ref "U7") (pin "G12") (pinfunction "VSS_G12") (pintype "passive"))
      (node (ref "U7") (pin "G2") (pinfunction "VSS_G2") (pintype "passive"))
      (node (ref "U7") (pin "G6") (pinfunction "VSS_G6") (pintype "passive"))
      (node (ref "U7") (pin "G7") (pinfunction "VSS_G7") (pintype "passive"))
      (node (ref "U7") (pin "G8") (pinfunction "VSS_G8") (pintype "passive"))
      (node (ref "U7") (pin "G9") (pinfunction "VSS_G9") (pintype "passive"))
      (node (ref "U7") (pin "H10") (pinfunction "VSS_H10") (pintype "passive"))
      (node (ref "U7") (pin "H12") (pinfunction "VSS_H12") (pintype "passive"))
      (node (ref "U7") (pin "H6") (pinfunction "VSS_H6") (pintype "passive"))
      (node (ref "U7") (pin "H7") (pinfunction "VSS_H7") (pintype "passive"))
      (node (ref "U7") (pin "H8") (pinfunction "VSS_H8") (pintype "passive"))
      (node (ref "U7") (pin "H9") (pinfunction "VSS_H9") (pintype "passive"))
      (node (ref "U7") (pin "J10") (pinfunction "VSS_J10") (pintype "passive"))
      (node (ref "U7") (pin "J6") (pinfunction "VSS_J6") (pintype "passive"))
      (node (ref "U7") (pin "J7") (pinfunction "VSS_J7") (pintype "passive"))
      (node (ref "U7") (pin "J8") (pinfunction "VSS_J8") (pintype "passive"))
      (node (ref "U7") (pin "J9") (pinfunction "VSS_J9") (pintype "passive"))
      (node (ref "U7") (pin "K10") (pinfunction "VSS_K10") (pintype "passive"))
      (node (ref "U7") (pin "K6") (pinfunction "VSS_K6") (pintype "passive"))
      (node (ref "U7") (pin "K7") (pinfunction "VSS_K7") (pintype "passive"))
      (node (ref "U7") (pin "K8") (pinfunction "VSS_K8") (pintype "passive"))
      (node (ref "U7") (pin "K9") (pinfunction "VSS_K9") (pintype "passive"))
      (node (ref "U7") (pin "M1") (pinfunction "VSSA_M1") (pintype "passive"))
      (node (ref "U7") (pin "M8") (pinfunction "VSS_M8") (pintype "passive"))
      (node (ref "U7") (pin "M9") (pinfunction "VSS_M9") (pintype "passive"))
      (node (ref "U7") (pin "N1") (pinfunction "VREF-_N1") (pintype "passive"))
      (node (ref "U8") (pin "2") (pinfunction "GND_2") (pintype "passive"))
      (node (ref "U9") (pin "2") (pinfunction "GND_2") (pintype "passive"))
      (node (ref "X1") (pin "2") (pinfunction "GND_2") (pintype "passive"))
    )
    (net (code "36") (name "Net-(D1-K)") (class "Default")
      (node (ref "C18") (pin "1") (pinfunction "1_1") (pintype "passive"))
      (node (ref "C20") (pin "2") (pinfunction "2_2") (pintype "passive"))
      (node (ref "D1") (pin "2") (pinfunction "K_2") (pintype "passive"))
      (node (ref "D2") (pin "2") (pinfunction "K_2") (pintype "passive"))
      (node (ref "D3") (pin "2") (pinfunction "K_2") (pintype "passive"))
      (node (ref "U9") (pin "1") (pinfunction "Vin_1") (pintype "passive"))
      (node (ref "U9") (pin "3") (pinfunction "CE_3") (pintype "passive"))
    )
    (net (code "37") (name "Net-(JP1-NO)") (class "Default")
      (node (ref "C28") (pin "2") (pinfunction "2_2") (pintype "passive"))
      (node (ref "JP1") (pin "2") (pinfunction "NO_2") (pintype "passive"))
      (node (ref "U7") (pin "J1") (pinfunction "NRST_J1") (pintype "passive"))
    )
    (net (code "38") (name "Net-(JP3-COMMON)") (class "Default")
      (node (ref "JP3") (pin "1") (pinfunction "COMMON_1") (pintype "passive"))
      (node (ref "R29") (pin "2") (pinfunction "2_2") (pintype "passive"))
    )
    (net (code "39") (name "Net-(LD4-Red_anode)") (class "Default")
      (node (ref "LD4") (pin "2") (pinfunction "Red_anode_2") (pintype "passive"))
      (node (ref "R9") (pin "1") (pinfunction "1_1") (pintype "passive"))
    )
    (net (code "40") (name "Net-(LD4-YellowGreen_cathode)") (class "Default")
      (node (ref "LD4") (pin "3") (pinfunction "YellowGreen_cathode_3") (pintype "passive"))
      (node (ref "R8") (pin "1") (pinfunction "1_1") (pintype "passive"))
    )
    (net (code "41") (name "Net-(LD6-Pad1)") (class "Default")
      (node (ref "LD6") (pin "1") (pintype "passive"))
      (node (ref "R2") (pin "1") (pinfunction "1_1") (pintype "passive"))
    )
    (net (code "42") (name "Net-(U1-B1)") (class "Default")
      (node (ref "R4") (pin "2") (pinfunction "2_2") (pintype "passive"))
      (node (ref "U1") (pin "7") (pinfunction "B1_7") (pintype "passive"))
    )
    (net (code "43") (name "Net-(U1-B2)") (class "Default")
      (node (ref "R3") (pin "2") (pinfunction "2_2") (pintype "passive"))
      (node (ref "U1") (pin "6") (pinfunction "B2_6") (pintype "passive"))
    )
    (net (code "44") (name "Net-(U2-~{FAULT})") (class "Default")
      (node (ref "LD6") (pin "2") (pintype "passive"))
      (node (ref "R1") (pin "1") (pinfunction "1_1") (pintype "passive"))
      (node (ref "U2") (pin "3") (pinfunction "~{FAULT}_3") (pintype "passive"))
    )
    (net (code "45") (name "Net-(U7A-OSC_IN{slash}PH0)") (class "Default")
      (node (ref "R21") (pin "2") (pinfunction "2_2") (pintype "passive"))
      (node (ref "U7") (pin "G1") (pinfunction "OSC_IN/PH0_G1") (pintype "passive"))
    )
    (net (code "46") (name "Net-(U7A-REXT_OTGPHY)") (class "Default")
      (node (ref "R6") (pin "2") (pinfunction "2_2") (pintype "passive"))
      (node (ref "U7") (pin "J15") (pinfunction "REXT_OTGPHY_J15") (pintype "passive"))
    )
    (net (code "47") (name "Net-(U7A-STLK_MCO{slash}PA8)") (class "Default")
      (node (ref "R5") (pin "1") (pinfunction "1_1") (pintype "passive"))
      (node (ref "U7") (pin "F15") (pinfunction "STLK_MCO/PA8_F15") (pintype "passive"))
    )
    (net (code "48") (name "Net-(U7A-T_VCC_AIN{slash}PA0)") (class "Default")
      (node (ref "R18") (pin "1") (pinfunction "1_1") (pintype "passive"))
      (node (ref "R20") (pin "1") (pinfunction "1_1") (pintype "passive"))
      (node (ref "U7") (pin "N3") (pinfunction "T_VCC_AIN/PA0_N3") (pintype "passive"))
    )
    (net (code "49") (name "Net-(U7A-V12_OTGPHY)") (class "Default")
      (node (ref "C7") (pin "2") (pinfunction "2_2") (pintype "passive"))
      (node (ref "U7") (pin "J14") (pinfunction "V12_OTGPHY_J14") (pintype "passive"))
    )
    (net (code "50") (name "Net-(U7B-BYPASS-REG)") (class "Default")
      (node (ref "R22") (pin "2") (pinfunction "2_2") (pintype "passive"))
      (node (ref "U7") (pin "L4") (pinfunction "BYPASS-REG_L4") (pintype "passive"))
    )
    (net (code "51") (name "Net-(U7B-VCAP1)") (class "Default")
      (node (ref "C13") (pin "2") (pinfunction "2_2") (pintype "passive"))
      (node (ref "U7") (pin "M10") (pinfunction "VCAP1_M10") (pintype "passive"))
    )
    (net (code "52") (name "Net-(U7B-VCAP2)") (class "Default")
      (node (ref "C12") (pin "2") (pinfunction "2_2") (pintype "passive"))
      (node (ref "U7") (pin "F13") (pinfunction "VCAP2_F13") (pintype "passive"))
    )
    (net (code "53") (name "Net-(U9-BYPASS)") (class "Default")
      (node (ref "C19") (pin "2") (pinfunction "2_2") (pintype "passive"))
      (node (ref "U9") (pin "4") (pinfunction "BYPASS_4") (pintype "passive"))
    )
    (net (code "54") (name "Net-(U10-B2)") (class "Default")
      (node (ref "R13") (pin "2") (pinfunction "2_2") (pintype "passive"))
      (node (ref "SB5") (pin "2") (pinfunction "2_2") (pintype "passive"))
      (node (ref "U10") (pin "6") (pinfunction "B2_6") (pintype "passive"))
    )
    (net (code "55") (name "Net-(X1-EN)") (class "Default")
      (node (ref "R24") (pin "2") (pinfunction "2_2") (pintype "passive"))
      (node (ref "X1") (pin "1") (pinfunction "EN_1") (pintype "passive"))
    )
    (net (code "56") (name "Net-(X1-OUT)") (class "Default")
      (node (ref "R21") (pin "1") (pinfunction "1_1") (pintype "passive"))
      (node (ref "X1") (pin "3") (pinfunction "OUT_3") (pintype "passive"))
    )
    (net (code "57") (name "VDD_MCU") (class "Default")
      (node (ref "C26") (pin "1") (pinfunction "1_1") (pintype "passive"))
      (node (ref "C4") (pin "1") (pinfunction "1_1") (pintype "passive"))
      (node (ref "R4") (pin "1") (pinfunction "1_1") (pintype "passive"))
      (node (ref "U1") (pin "8") (pinfunction "VccB_8") (pintype "power_in"))
      (node (ref "U10") (pin "8") (pinfunction "VccB_8") (pintype "power_in"))
    )
    (net (code "58") (name "unconnected-(CN1-ID-Pad4)") (class "Default")
      (node (ref "CN1") (pin "4") (pinfunction "ID_4") (pintype "passive+no_connect"))
    )
    (net (code "59") (name "unconnected-(CN5-Pad1)") (class "Default")
      (node (ref "CN5") (pin "1") (pinfunction "1_1") (pintype "passive+no_connect"))
    )
    (net (code "60") (name "unconnected-(CN5-Pad2)") (class "Default")
      (node (ref "CN5") (pin "2") (pinfunction "2_2") (pintype "passive+no_connect"))
    )
    (net (code "61") (name "unconnected-(CN5-Pad9)") (class "Default")
      (node (ref "CN5") (pin "9") (pinfunction "9_9") (pintype "passive+no_connect"))
    )
    (net (code "62") (name "unconnected-(U1-A1-Pad2)") (class "Default")
      (node (ref "U1") (pin "2") (pinfunction "A1_2") (pintype "passive+no_connect"))
    )
    (net (code "63") (name "unconnected-(U5-NC-Pad4)") (class "Default")
      (node (ref "U5") (pin "4") (pinfunction "NC_4") (pintype "passive+no_connect"))
    )
    (net (code "64") (name "unconnected-(U7A-HW_TYP_0{slash}PI4-PadD4)") (class "Default")
      (node (ref "U7") (pin "D4") (pinfunction "HW_TYP_0/PI4_D4") (pintype "passive+no_connect"))
    )
    (net (code "65") (name "unconnected-(U7A-HW_TYP_1{slash}PI5-PadC4)") (class "Default")
      (node (ref "U7") (pin "C4") (pinfunction "HW_TYP_1/PI5_C4") (pintype "passive+no_connect"))
    )
    (net (code "66") (name "unconnected-(U7A-OSC_OUT{slash}PH1-PadH1)") (class "Default")
      (node (ref "U7") (pin "H1") (pinfunction "OSC_OUT/PH1_H1") (pintype "passive+no_connect"))
    )
    (net (code "67") (name "unconnected-(U7A-T_SW_DIR{slash}PA7-PadR3)") (class "Default")
      (node (ref "U7") (pin "R3") (pinfunction "T_SW_DIR/PA7_R3") (pintype "passive+no_connect"))
    )
    (net (code "68") (name "unconnected-(U24-IO3-Pad4)") (class "Default")
      (node (ref "U24") (pin "4") (pinfunction "IO3_4") (pintype "passive+no_connect"))
    )
  )
)
